# v2RespiratorCOVID19.net
KiCad netlist of a schematic drawn in EAGLE
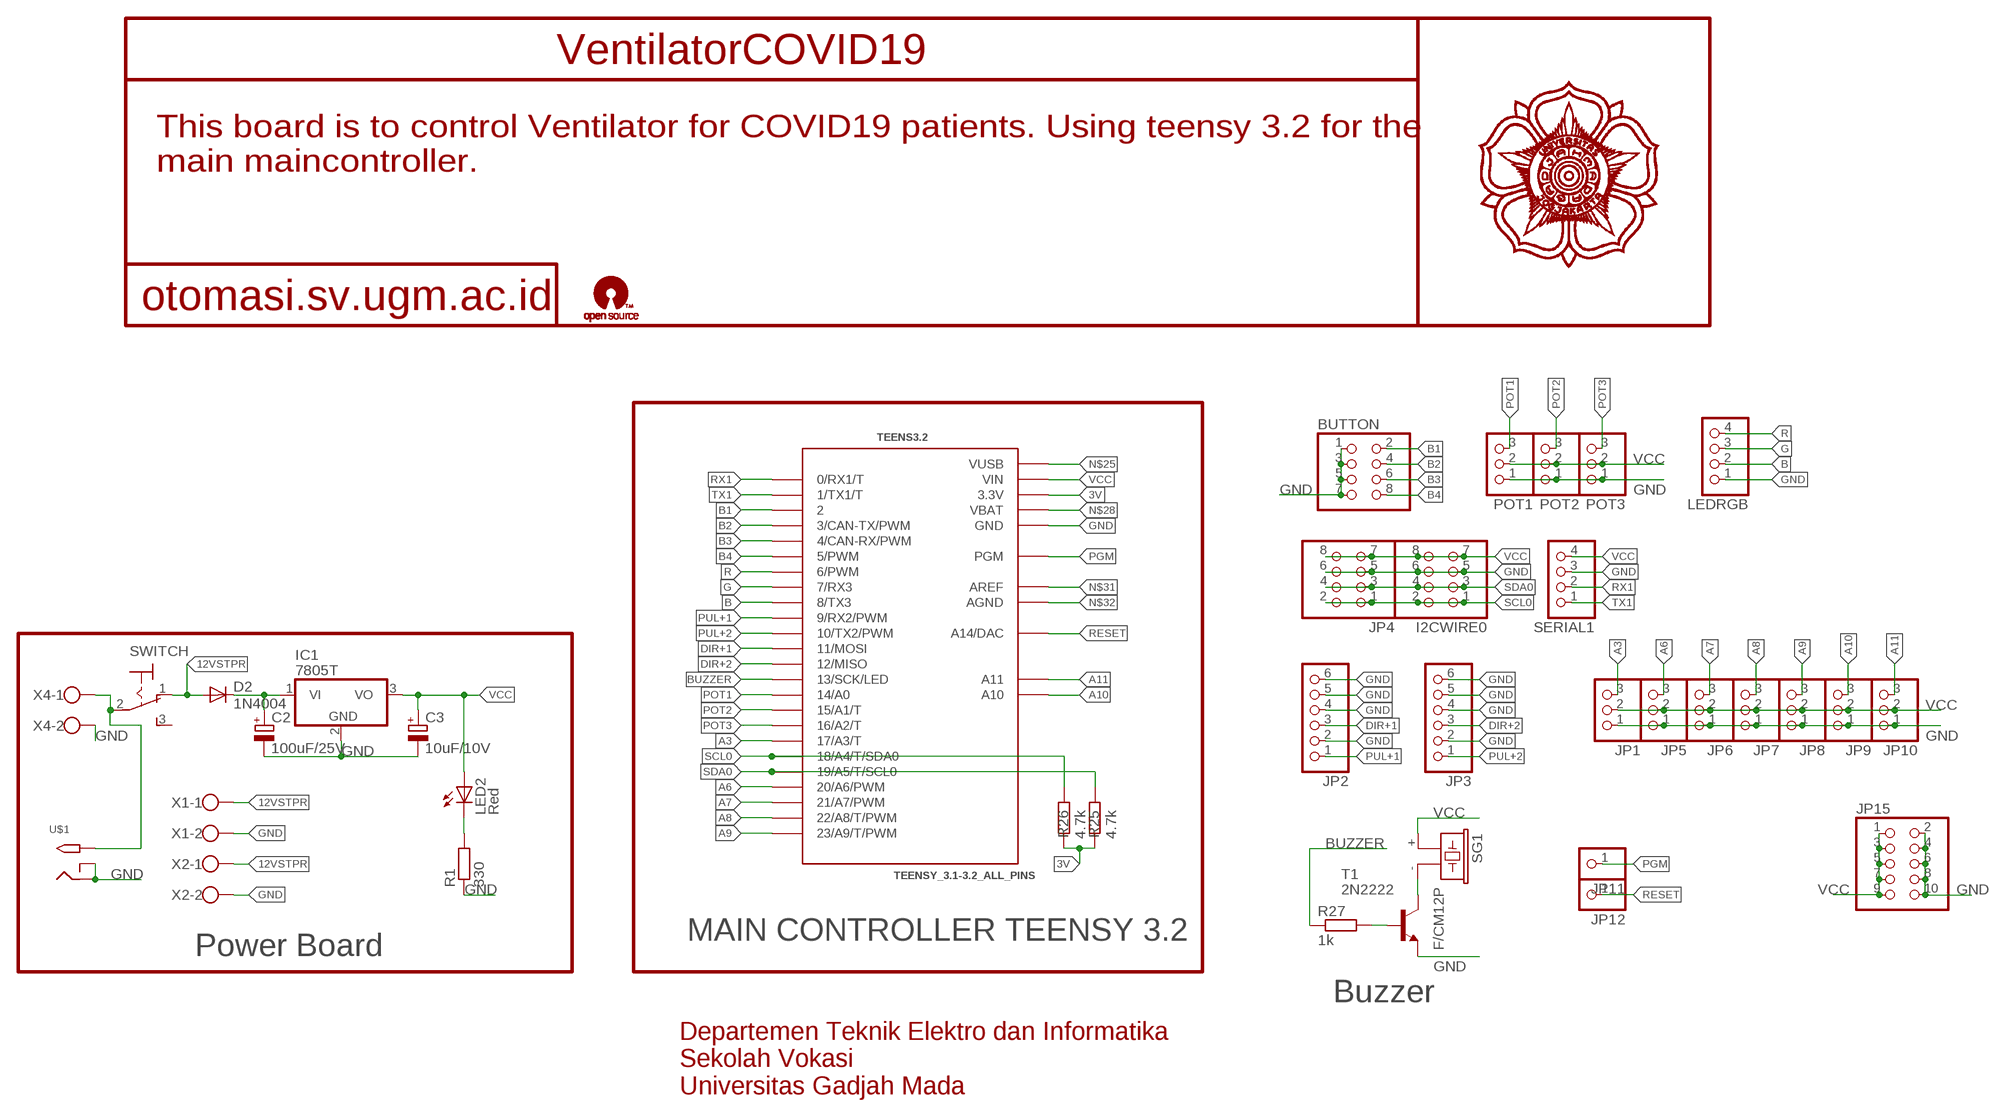
[diagram p0: schematic, sheet 1]

(export (version "E")
  (design (tool "Eeschema 10.0.6"))
  (components
    (comp (ref "BUTTON")
      (value "PINHD-2X4")
      (footprint "eagle-import:2X04")
      (libsource (lib "eagle-import") (part "PINHD-2X4"))
    )
    (comp (ref "C2")
      (value "100uF/25V")
      (footprint "eagle-import:E5-8,5")
      (libsource (lib "eagle-import") (part "CPOL-EUE5-8.5"))
    )
    (comp (ref "C3")
      (value "10uF/10V")
      (footprint "eagle-import:E5-8,5")
      (libsource (lib "eagle-import") (part "CPOL-EUE5-8.5"))
    )
    (comp (ref "D2")
      (value "1N4004")
      (footprint "eagle-import:DO41-10")
      (libsource (lib "eagle-import") (part "1N4004"))
    )
    (comp (ref "I2CWIRE0")
      (value "PINHD-2X4")
      (footprint "eagle-import:2X04")
      (libsource (lib "eagle-import") (part "PINHD-2X4"))
    )
    (comp (ref "IC1")
      (value "7805T")
      (footprint "eagle-import:TO220H")
      (libsource (lib "eagle-import") (part "78T05"))
    )
    (comp (ref "JP1")
      (value "PINHD-1X3")
      (footprint "eagle-import:1X03")
      (libsource (lib "eagle-import") (part "pinhead_PINHD-1X3"))
    )
    (comp (ref "JP2")
      (value "PINHD-1X6")
      (footprint "eagle-import:1X06")
      (libsource (lib "eagle-import") (part "PINHD-1X6"))
    )
    (comp (ref "JP3")
      (value "PINHD-1X6")
      (footprint "eagle-import:1X06")
      (libsource (lib "eagle-import") (part "PINHD-1X6"))
    )
    (comp (ref "JP4")
      (value "PINHD-2X4")
      (footprint "eagle-import:2X04")
      (libsource (lib "eagle-import") (part "PINHD-2X4"))
    )
    (comp (ref "JP5")
      (value "PINHD-1X3")
      (footprint "eagle-import:1X03")
      (libsource (lib "eagle-import") (part "pinhead_PINHD-1X3"))
    )
    (comp (ref "JP6")
      (value "PINHD-1X3")
      (footprint "eagle-import:1X03")
      (libsource (lib "eagle-import") (part "pinhead_PINHD-1X3"))
    )
    (comp (ref "JP7")
      (value "PINHD-1X3")
      (footprint "eagle-import:1X03")
      (libsource (lib "eagle-import") (part "pinhead_PINHD-1X3"))
    )
    (comp (ref "JP8")
      (value "PINHD-1X3")
      (footprint "eagle-import:1X03")
      (libsource (lib "eagle-import") (part "pinhead_PINHD-1X3"))
    )
    (comp (ref "JP9")
      (value "PINHD-1X3")
      (footprint "eagle-import:1X03")
      (libsource (lib "eagle-import") (part "pinhead_PINHD-1X3"))
    )
    (comp (ref "JP10")
      (value "PINHD-1X3")
      (footprint "eagle-import:1X03")
      (libsource (lib "eagle-import") (part "pinhead_PINHD-1X3"))
    )
    (comp (ref "JP11")
      (value "PINHD-1X1")
      (footprint "eagle-import:1X01")
      (libsource (lib "eagle-import") (part "PINHD-1X1"))
    )
    (comp (ref "JP12")
      (value "PINHD-1X1")
      (footprint "eagle-import:1X01")
      (libsource (lib "eagle-import") (part "PINHD-1X1"))
    )
    (comp (ref "JP15")
      (value "PINHD-2X5")
      (footprint "eagle-import:2X05")
      (libsource (lib "eagle-import") (part "PINHD-2X5"))
    )
    (comp (ref "LED2")
      (value "Red")
      (footprint "eagle-import:LED3MM")
      (libsource (lib "eagle-import") (part "LED3MM"))
    )
    (comp (ref "LEDRGB")
      (value "PINHD-1X4")
      (footprint "eagle-import:1X04")
      (libsource (lib "eagle-import") (part "PINHD-1X4"))
    )
    (comp (ref "POT1")
      (value "PINHD-1X3")
      (footprint "eagle-import:1X03")
      (libsource (lib "eagle-import") (part "PINHD-1X3"))
    )
    (comp (ref "POT2")
      (value "PINHD-1X3")
      (footprint "eagle-import:1X03")
      (libsource (lib "eagle-import") (part "PINHD-1X3"))
    )
    (comp (ref "POT3")
      (value "PINHD-1X3")
      (footprint "eagle-import:1X03")
      (libsource (lib "eagle-import") (part "PINHD-1X3"))
    )
    (comp (ref "R1")
      (value "330")
      (footprint "eagle-import:R1206")
      (libsource (lib "eagle-import") (part "R-EU_R1206"))
    )
    (comp (ref "R25")
      (value "4.7k")
      (footprint "eagle-import:R1206")
      (libsource (lib "eagle-import") (part "R-EU_R1206"))
    )
    (comp (ref "R26")
      (value "4.7k")
      (footprint "eagle-import:R1206")
      (libsource (lib "eagle-import") (part "R-EU_R1206"))
    )
    (comp (ref "R27")
      (value "1k")
      (footprint "eagle-import:R1206")
      (libsource (lib "eagle-import") (part "R-EU_R1206"))
    )
    (comp (ref "SERIAL1")
      (value "PINHD-1X4")
      (footprint "eagle-import:1X04")
      (libsource (lib "eagle-import") (part "PINHD-1X4"))
    )
    (comp (ref "SG1")
      (value "F/CM12P")
      (footprint "eagle-import:F_CM12P")
      (libsource (lib "eagle-import") (part "F/CM12P"))
    )
    (comp (ref "SWITCH")
      (value "M9040P")
      (footprint "eagle-import:M9040P")
      (libsource (lib "eagle-import") (part "M9040P"))
    )
    (comp (ref "T1")
      (value "2N2222")
      (footprint "eagle-import:TO92-EBC-OVAL")
      (libsource (lib "eagle-import") (part "2N2222"))
    )
    (comp (ref "TEENS3.2")
      (value "TEENSY_3.1-3.2_ALL_PINS")
      (footprint "eagle-import:TEENSY_3.0-3.2&LC_ALL_PINS")
      (libsource (lib "eagle-import") (part "TEENSY_3.1-3.2_ALL_PINS"))
    )
    (comp (ref "U$1")
      (value "2.1MMJACKTHM")
      (footprint "eagle-import:PJ-102A")
      (libsource (lib "eagle-import") (part "2.1MMJACKTHM"))
    )
    (comp (ref "X1")
      (value "W237-102")
      (footprint "eagle-import:W237-102")
      (fields (field (name "MPN") "237-102"))
      (libsource (lib "eagle-import") (part "W237-102"))
    )
    (comp (ref "X2")
      (value "W237-102")
      (footprint "eagle-import:W237-102")
      (fields (field (name "MPN") "237-102"))
      (libsource (lib "eagle-import") (part "W237-102"))
    )
    (comp (ref "X4")
      (value "W237-102")
      (footprint "eagle-import:W237-102")
      (fields (field (name "MPN") "237-102"))
      (libsource (lib "eagle-import") (part "W237-102"))
    )
  )
  (nets
    (net (code "1") (name "3V") (class "Default")
      (node (ref "R25") (pin "2") (pinfunction "2_2") (pintype "passive"))
      (node (ref "R26") (pin "2") (pinfunction "2_2") (pintype "passive"))
      (node (ref "TEENS3.2") (pin "3.3V") (pinfunction "3.3V_3.3V") (pintype "power_in"))
      (node (ref "TEENS3.2") (pin "3.3V1") (pinfunction "3.3V_3.3V1") (pintype "power_in"))
    )
    (net (code "2") (name "12VSTPR") (class "Default")
      (node (ref "D2") (pin "A") (pinfunction "A_A") (pintype "passive"))
      (node (ref "SWITCH") (pin "1") (pinfunction "O_1") (pintype "passive"))
      (node (ref "X1") (pin "1") (pinfunction "KL_1") (pintype "passive"))
      (node (ref "X2") (pin "1") (pinfunction "KL_1") (pintype "passive"))
    )
    (net (code "3") (name "A3") (class "Default")
      (node (ref "JP1") (pin "3") (pinfunction "3_3") (pintype "passive"))
      (node (ref "TEENS3.2") (pin "17/A3") (pinfunction "17/A3/T_17/A3") (pintype "bidirectional"))
    )
    (net (code "4") (name "A6") (class "Default")
      (node (ref "JP5") (pin "3") (pinfunction "3_3") (pintype "passive"))
      (node (ref "TEENS3.2") (pin "20/A6") (pinfunction "20/A6/PWM_20/A6") (pintype "bidirectional"))
    )
    (net (code "5") (name "A7") (class "Default")
      (node (ref "JP6") (pin "3") (pinfunction "3_3") (pintype "passive"))
      (node (ref "TEENS3.2") (pin "21/A7") (pinfunction "21/A7/PWM_21/A7") (pintype "bidirectional"))
    )
    (net (code "6") (name "A8") (class "Default")
      (node (ref "JP7") (pin "3") (pinfunction "3_3") (pintype "passive"))
      (node (ref "TEENS3.2") (pin "22/A8") (pinfunction "22/A8/T/PWM_22/A8") (pintype "bidirectional"))
    )
    (net (code "7") (name "A9") (class "Default")
      (node (ref "JP8") (pin "3") (pinfunction "3_3") (pintype "passive"))
      (node (ref "TEENS3.2") (pin "23/A9") (pinfunction "23/A9/T/PWM_23/A9") (pintype "bidirectional"))
    )
    (net (code "8") (name "A10") (class "Default")
      (node (ref "JP9") (pin "3") (pinfunction "3_3") (pintype "passive"))
      (node (ref "TEENS3.2") (pin "A10") (pinfunction "A10_A10") (pintype "bidirectional"))
    )
    (net (code "9") (name "A11") (class "Default")
      (node (ref "JP10") (pin "3") (pinfunction "3_3") (pintype "passive"))
      (node (ref "TEENS3.2") (pin "A11") (pinfunction "A11_A11") (pintype "bidirectional"))
    )
    (net (code "10") (name "B") (class "Default")
      (node (ref "LEDRGB") (pin "2") (pinfunction "2_2") (pintype "passive"))
      (node (ref "TEENS3.2") (pin "8") (pinfunction "8/TX3_8") (pintype "bidirectional"))
    )
    (net (code "11") (name "B1") (class "Default")
      (node (ref "BUTTON") (pin "2") (pinfunction "2_2") (pintype "passive"))
      (node (ref "TEENS3.2") (pin "2") (pinfunction "2_2") (pintype "bidirectional"))
    )
    (net (code "12") (name "B2") (class "Default")
      (node (ref "BUTTON") (pin "4") (pinfunction "4_4") (pintype "passive"))
      (node (ref "TEENS3.2") (pin "3") (pinfunction "3/CAN-TX/PWM_3") (pintype "bidirectional"))
    )
    (net (code "13") (name "B3") (class "Default")
      (node (ref "BUTTON") (pin "6") (pinfunction "6_6") (pintype "passive"))
      (node (ref "TEENS3.2") (pin "4") (pinfunction "4/CAN-RX/PWM_4") (pintype "bidirectional"))
    )
    (net (code "14") (name "B4") (class "Default")
      (node (ref "BUTTON") (pin "8") (pinfunction "8_8") (pintype "passive"))
      (node (ref "TEENS3.2") (pin "5") (pinfunction "5/PWM_5") (pintype "bidirectional"))
    )
    (net (code "15") (name "BUZZER") (class "Default")
      (node (ref "R27") (pin "1") (pinfunction "1_1") (pintype "passive"))
      (node (ref "TEENS3.2") (pin "13") (pinfunction "13/SCK/LED_13") (pintype "bidirectional"))
    )
    (net (code "16") (name "DIR+1") (class "Default")
      (node (ref "JP2") (pin "3") (pinfunction "3_3") (pintype "passive"))
      (node (ref "TEENS3.2") (pin "11") (pinfunction "11/MOSI_11") (pintype "bidirectional"))
    )
    (net (code "17") (name "DIR+2") (class "Default")
      (node (ref "JP3") (pin "3") (pinfunction "3_3") (pintype "passive"))
      (node (ref "TEENS3.2") (pin "12") (pinfunction "12/MISO_12") (pintype "bidirectional"))
    )
    (net (code "18") (name "G") (class "Default")
      (node (ref "LEDRGB") (pin "3") (pinfunction "3_3") (pintype "passive"))
      (node (ref "TEENS3.2") (pin "7") (pinfunction "7/RX3_7") (pintype "bidirectional"))
    )
    (net (code "19") (name "GND") (class "Default")
      (node (ref "BUTTON") (pin "1") (pinfunction "1_1") (pintype "passive"))
      (node (ref "BUTTON") (pin "3") (pinfunction "3_3") (pintype "passive"))
      (node (ref "BUTTON") (pin "5") (pinfunction "5_5") (pintype "passive"))
      (node (ref "BUTTON") (pin "7") (pinfunction "7_7") (pintype "passive"))
      (node (ref "C2") (pin "-") (pinfunction "-_-") (pintype "passive"))
      (node (ref "C3") (pin "-") (pinfunction "-_-") (pintype "passive"))
      (node (ref "I2CWIRE0") (pin "5") (pinfunction "5_5") (pintype "passive"))
      (node (ref "I2CWIRE0") (pin "6") (pinfunction "6_6") (pintype "passive"))
      (node (ref "IC1") (pin "2") (pinfunction "GND_2") (pintype "passive"))
      (node (ref "JP1") (pin "1") (pinfunction "1_1") (pintype "passive"))
      (node (ref "JP10") (pin "1") (pinfunction "1_1") (pintype "passive"))
      (node (ref "JP15") (pin "10") (pinfunction "10_10") (pintype "passive"))
      (node (ref "JP15") (pin "2") (pinfunction "2_2") (pintype "passive"))
      (node (ref "JP15") (pin "4") (pinfunction "4_4") (pintype "passive"))
      (node (ref "JP15") (pin "6") (pinfunction "6_6") (pintype "passive"))
      (node (ref "JP15") (pin "8") (pinfunction "8_8") (pintype "passive"))
      (node (ref "JP2") (pin "2") (pinfunction "2_2") (pintype "passive"))
      (node (ref "JP2") (pin "4") (pinfunction "4_4") (pintype "passive"))
      (node (ref "JP2") (pin "5") (pinfunction "5_5") (pintype "passive"))
      (node (ref "JP2") (pin "6") (pinfunction "6_6") (pintype "passive"))
      (node (ref "JP3") (pin "2") (pinfunction "2_2") (pintype "passive"))
      (node (ref "JP3") (pin "4") (pinfunction "4_4") (pintype "passive"))
      (node (ref "JP3") (pin "5") (pinfunction "5_5") (pintype "passive"))
      (node (ref "JP3") (pin "6") (pinfunction "6_6") (pintype "passive"))
      (node (ref "JP4") (pin "5") (pinfunction "5_5") (pintype "passive"))
      (node (ref "JP4") (pin "6") (pinfunction "6_6") (pintype "passive"))
      (node (ref "JP5") (pin "1") (pinfunction "1_1") (pintype "passive"))
      (node (ref "JP6") (pin "1") (pinfunction "1_1") (pintype "passive"))
      (node (ref "JP7") (pin "1") (pinfunction "1_1") (pintype "passive"))
      (node (ref "JP8") (pin "1") (pinfunction "1_1") (pintype "passive"))
      (node (ref "JP9") (pin "1") (pinfunction "1_1") (pintype "passive"))
      (node (ref "LEDRGB") (pin "1") (pinfunction "1_1") (pintype "passive"))
      (node (ref "POT1") (pin "1") (pinfunction "1_1") (pintype "passive"))
      (node (ref "POT2") (pin "1") (pinfunction "1_1") (pintype "passive"))
      (node (ref "POT3") (pin "1") (pinfunction "1_1") (pintype "passive"))
      (node (ref "R1") (pin "1") (pinfunction "1_1") (pintype "passive"))
      (node (ref "SERIAL1") (pin "3") (pinfunction "3_3") (pintype "passive"))
      (node (ref "T1") (pin "E") (pinfunction "E_E") (pintype "passive"))
      (node (ref "TEENS3.2") (pin "GND") (pinfunction "GND_GND") (pintype "power_in"))
      (node (ref "TEENS3.2") (pin "GND1") (pinfunction "GND_GND1") (pintype "power_in"))
      (node (ref "U$1") (pin "RING") (pinfunction "RING_RING") (pintype "bidirectional"))
      (node (ref "U$1") (pin "RING_SW") (pinfunction "RING_SW_RING_SW") (pintype "bidirectional"))
      (node (ref "X1") (pin "2") (pinfunction "KL_2") (pintype "passive"))
      (node (ref "X2") (pin "2") (pinfunction "KL_2") (pintype "passive"))
      (node (ref "X4") (pin "2") (pinfunction "KL_2") (pintype "passive"))
    )
    (net (code "20") (name "N$25") (class "Default")
      (node (ref "TEENS3.2") (pin "VUSB") (pinfunction "VUSB_VUSB") (pintype "power_in"))
    )
    (net (code "21") (name "N$28") (class "Default")
      (node (ref "TEENS3.2") (pin "VBAT") (pinfunction "VBAT_VBAT") (pintype "power_in"))
    )
    (net (code "22") (name "N$31") (class "Default")
      (node (ref "TEENS3.2") (pin "AREF") (pinfunction "AREF_AREF") (pintype "power_in"))
    )
    (net (code "23") (name "N$32") (class "Default")
      (node (ref "TEENS3.2") (pin "AGND") (pinfunction "AGND_AGND") (pintype "power_in"))
    )
    (net (code "24") (name "Net-(IC1-VI)") (class "Default")
      (node (ref "C2") (pin "+") (pinfunction "+_+") (pintype "passive"))
      (node (ref "D2") (pin "C") (pinfunction "C_C") (pintype "passive"))
      (node (ref "IC1") (pin "1") (pinfunction "VI_1") (pintype "input"))
    )
    (net (code "25") (name "Net-(LED2-C)") (class "Default")
      (node (ref "LED2") (pin "K") (pinfunction "C_K") (pintype "passive"))
      (node (ref "R1") (pin "2") (pinfunction "2_2") (pintype "passive"))
    )
    (net (code "26") (name "Net-(R27-Pad2)") (class "Default")
      (node (ref "R27") (pin "2") (pinfunction "2_2") (pintype "passive"))
      (node (ref "T1") (pin "B") (pinfunction "B_B") (pintype "passive"))
    )
    (net (code "27") (name "Net-(SG1-2)") (class "Default")
      (node (ref "SG1") (pin "-") (pinfunction "2_-") (pintype "passive"))
      (node (ref "T1") (pin "C") (pinfunction "C_C") (pintype "passive"))
    )
    (net (code "28") (name "Net-(SWITCH-P)") (class "Default")
      (node (ref "SWITCH") (pin "2") (pinfunction "P_2") (pintype "passive"))
      (node (ref "U$1") (pin "TIP") (pinfunction "TIP_TIP") (pintype "bidirectional"))
      (node (ref "X4") (pin "1") (pinfunction "KL_1") (pintype "passive"))
    )
    (net (code "29") (name "PGM") (class "Default")
      (node (ref "JP11") (pin "1") (pinfunction "1_1") (pintype "passive"))
      (node (ref "TEENS3.2") (pin "PGM") (pinfunction "PGM_PGM") (pintype "bidirectional"))
    )
    (net (code "30") (name "POT1") (class "Default")
      (node (ref "POT1") (pin "3") (pinfunction "3_3") (pintype "passive"))
      (node (ref "TEENS3.2") (pin "14/A0") (pinfunction "14/A0_14/A0") (pintype "bidirectional"))
    )
    (net (code "31") (name "POT2") (class "Default")
      (node (ref "POT2") (pin "3") (pinfunction "3_3") (pintype "passive"))
      (node (ref "TEENS3.2") (pin "15/A1") (pinfunction "15/A1/T_15/A1") (pintype "bidirectional"))
    )
    (net (code "32") (name "POT3") (class "Default")
      (node (ref "POT3") (pin "3") (pinfunction "3_3") (pintype "passive"))
      (node (ref "TEENS3.2") (pin "16/A2") (pinfunction "16/A2/T_16/A2") (pintype "bidirectional"))
    )
    (net (code "33") (name "PUL+1") (class "Default")
      (node (ref "JP2") (pin "1") (pinfunction "1_1") (pintype "passive"))
      (node (ref "TEENS3.2") (pin "9") (pinfunction "9/RX2/PWM_9") (pintype "bidirectional"))
    )
    (net (code "34") (name "PUL+2") (class "Default")
      (node (ref "JP3") (pin "1") (pinfunction "1_1") (pintype "passive"))
      (node (ref "TEENS3.2") (pin "10") (pinfunction "10/TX2/PWM_10") (pintype "bidirectional"))
    )
    (net (code "35") (name "R") (class "Default")
      (node (ref "LEDRGB") (pin "4") (pinfunction "4_4") (pintype "passive"))
      (node (ref "TEENS3.2") (pin "6") (pinfunction "6/PWM_6") (pintype "bidirectional"))
    )
    (net (code "36") (name "RESET") (class "Default")
      (node (ref "JP12") (pin "1") (pinfunction "1_1") (pintype "passive"))
      (node (ref "TEENS3.2") (pin "RESET/DAC") (pinfunction "A14/DAC_RESET/DAC") (pintype "bidirectional"))
    )
    (net (code "37") (name "RX1") (class "Default")
      (node (ref "SERIAL1") (pin "2") (pinfunction "2_2") (pintype "passive"))
      (node (ref "TEENS3.2") (pin "0") (pinfunction "0/RX1/T_0") (pintype "bidirectional"))
    )
    (net (code "38") (name "SCL0") (class "Default")
      (node (ref "I2CWIRE0") (pin "1") (pinfunction "1_1") (pintype "passive"))
      (node (ref "I2CWIRE0") (pin "2") (pinfunction "2_2") (pintype "passive"))
      (node (ref "JP4") (pin "1") (pinfunction "1_1") (pintype "passive"))
      (node (ref "JP4") (pin "2") (pinfunction "2_2") (pintype "passive"))
      (node (ref "R26") (pin "1") (pinfunction "1_1") (pintype "passive"))
      (node (ref "TEENS3.2") (pin "18/A4") (pinfunction "18/A4/T/SDA0_18/A4") (pintype "bidirectional"))
    )
    (net (code "39") (name "SDA0") (class "Default")
      (node (ref "I2CWIRE0") (pin "3") (pinfunction "3_3") (pintype "passive"))
      (node (ref "I2CWIRE0") (pin "4") (pinfunction "4_4") (pintype "passive"))
      (node (ref "JP4") (pin "3") (pinfunction "3_3") (pintype "passive"))
      (node (ref "JP4") (pin "4") (pinfunction "4_4") (pintype "passive"))
      (node (ref "R25") (pin "1") (pinfunction "1_1") (pintype "passive"))
      (node (ref "TEENS3.2") (pin "19/A5") (pinfunction "19/A5/T/SCL0_19/A5") (pintype "bidirectional"))
    )
    (net (code "40") (name "TX1") (class "Default")
      (node (ref "SERIAL1") (pin "1") (pinfunction "1_1") (pintype "passive"))
      (node (ref "TEENS3.2") (pin "1") (pinfunction "1/TX1/T_1") (pintype "bidirectional"))
    )
    (net (code "41") (name "VCC") (class "Default")
      (node (ref "C3") (pin "+") (pinfunction "+_+") (pintype "passive"))
      (node (ref "I2CWIRE0") (pin "7") (pinfunction "7_7") (pintype "passive"))
      (node (ref "I2CWIRE0") (pin "8") (pinfunction "8_8") (pintype "passive"))
      (node (ref "IC1") (pin "3") (pinfunction "VO_3") (pintype "passive"))
      (node (ref "JP1") (pin "2") (pinfunction "2_2") (pintype "passive"))
      (node (ref "JP10") (pin "2") (pinfunction "2_2") (pintype "passive"))
      (node (ref "JP15") (pin "1") (pinfunction "1_1") (pintype "passive"))
      (node (ref "JP15") (pin "3") (pinfunction "3_3") (pintype "passive"))
      (node (ref "JP15") (pin "5") (pinfunction "5_5") (pintype "passive"))
      (node (ref "JP15") (pin "7") (pinfunction "7_7") (pintype "passive"))
      (node (ref "JP15") (pin "9") (pinfunction "9_9") (pintype "passive"))
      (node (ref "JP4") (pin "7") (pinfunction "7_7") (pintype "passive"))
      (node (ref "JP4") (pin "8") (pinfunction "8_8") (pintype "passive"))
      (node (ref "JP5") (pin "2") (pinfunction "2_2") (pintype "passive"))
      (node (ref "JP6") (pin "2") (pinfunction "2_2") (pintype "passive"))
      (node (ref "JP7") (pin "2") (pinfunction "2_2") (pintype "passive"))
      (node (ref "JP8") (pin "2") (pinfunction "2_2") (pintype "passive"))
      (node (ref "JP9") (pin "2") (pinfunction "2_2") (pintype "passive"))
      (node (ref "LED2") (pin "A") (pinfunction "A_A") (pintype "passive"))
      (node (ref "POT1") (pin "2") (pinfunction "2_2") (pintype "passive"))
      (node (ref "POT2") (pin "2") (pinfunction "2_2") (pintype "passive"))
      (node (ref "POT3") (pin "2") (pinfunction "2_2") (pintype "passive"))
      (node (ref "SERIAL1") (pin "4") (pinfunction "4_4") (pintype "passive"))
      (node (ref "SG1") (pin "+") (pinfunction "1_+") (pintype "passive"))
      (node (ref "TEENS3.2") (pin "VIN") (pinfunction "VIN_VIN") (pintype "power_in"))
    )
    (net (code "42") (name "unconnected-(SWITCH-S-Pad3)") (class "Default")
      (node (ref "SWITCH") (pin "3") (pinfunction "S_3") (pintype "passive"))
    )
  )
)
